# test_strip_v0_1_r1_2.net
KiCad netlist of a schematic drawn in EAGLE
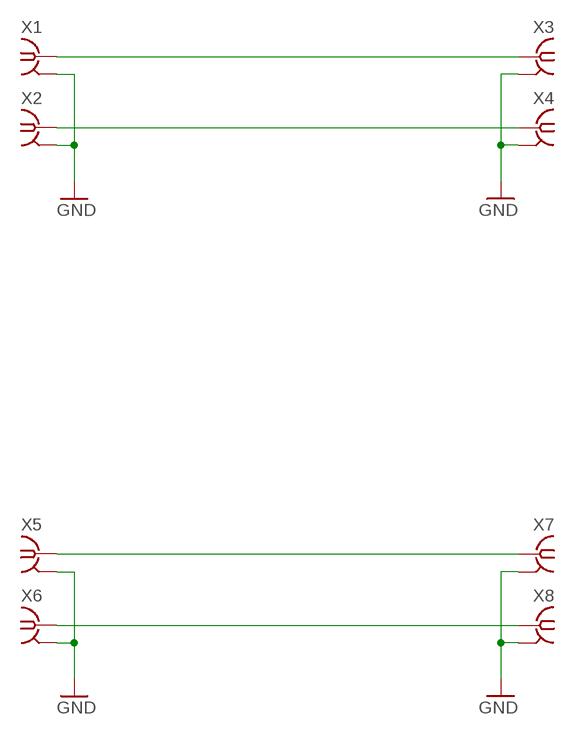
[diagram p0: schematic, sheet 1]

(export (version "E")
  (design (tool "Eeschema 10.0.6"))
  (components
    (comp (ref "X1")
      (value "BU-SMA-E-ND")
      (footprint "eagle-import:SMA-EDGE_ND")
      (libsource (lib "eagle-import") (part "BU-SMA-E-ND"))
    )
    (comp (ref "X2")
      (value "BU-SMA-E-ND")
      (footprint "eagle-import:SMA-EDGE_ND")
      (libsource (lib "eagle-import") (part "BU-SMA-E-ND"))
    )
    (comp (ref "X3")
      (value "BU-SMA-E-ND")
      (footprint "eagle-import:SMA-EDGE_ND")
      (libsource (lib "eagle-import") (part "BU-SMA-E-ND"))
    )
    (comp (ref "X4")
      (value "BU-SMA-E-ND")
      (footprint "eagle-import:SMA-EDGE_ND")
      (libsource (lib "eagle-import") (part "BU-SMA-E-ND"))
    )
    (comp (ref "X5")
      (value "BU-SMA-E-ND")
      (footprint "eagle-import:SMA-EDGE_ND")
      (libsource (lib "eagle-import") (part "BU-SMA-E-ND"))
    )
    (comp (ref "X6")
      (value "BU-SMA-E-ND")
      (footprint "eagle-import:SMA-EDGE_ND")
      (libsource (lib "eagle-import") (part "BU-SMA-E-ND"))
    )
    (comp (ref "X7")
      (value "BU-SMA-E-ND")
      (footprint "eagle-import:SMA-EDGE_ND")
      (libsource (lib "eagle-import") (part "BU-SMA-E-ND"))
    )
    (comp (ref "X8")
      (value "BU-SMA-E-ND")
      (footprint "eagle-import:SMA-EDGE_ND")
      (libsource (lib "eagle-import") (part "BU-SMA-E-ND"))
    )
  )
  (nets
    (net (code "1") (name "GND") (class "Default")
      (node (ref "X1") (pin "2@3") (pinfunction "2_2@3") (pintype "passive"))
      (node (ref "X1") (pin "2@4") (pinfunction "2_2@4") (pintype "passive"))
      (node (ref "X2") (pin "2@3") (pinfunction "2_2@3") (pintype "passive"))
      (node (ref "X2") (pin "2@4") (pinfunction "2_2@4") (pintype "passive"))
      (node (ref "X3") (pin "2@3") (pinfunction "2_2@3") (pintype "passive"))
      (node (ref "X3") (pin "2@4") (pinfunction "2_2@4") (pintype "passive"))
      (node (ref "X4") (pin "2@3") (pinfunction "2_2@3") (pintype "passive"))
      (node (ref "X4") (pin "2@4") (pinfunction "2_2@4") (pintype "passive"))
      (node (ref "X5") (pin "2@3") (pinfunction "2_2@3") (pintype "passive"))
      (node (ref "X5") (pin "2@4") (pinfunction "2_2@4") (pintype "passive"))
      (node (ref "X6") (pin "2@3") (pinfunction "2_2@3") (pintype "passive"))
      (node (ref "X6") (pin "2@4") (pinfunction "2_2@4") (pintype "passive"))
      (node (ref "X7") (pin "2@3") (pinfunction "2_2@3") (pintype "passive"))
      (node (ref "X7") (pin "2@4") (pinfunction "2_2@4") (pintype "passive"))
      (node (ref "X8") (pin "2@3") (pinfunction "2_2@3") (pintype "passive"))
      (node (ref "X8") (pin "2@4") (pinfunction "2_2@4") (pintype "passive"))
    )
    (net (code "2") (name "Net-(X1-Pad1)") (class "Default")
      (node (ref "X1") (pin "1") (pinfunction "1_1") (pintype "passive"))
      (node (ref "X3") (pin "1") (pinfunction "1_1") (pintype "passive"))
    )
    (net (code "3") (name "Net-(X2-Pad1)") (class "Default")
      (node (ref "X2") (pin "1") (pinfunction "1_1") (pintype "passive"))
      (node (ref "X4") (pin "1") (pinfunction "1_1") (pintype "passive"))
    )
    (net (code "4") (name "Net-(X5-Pad1)") (class "Default")
      (node (ref "X5") (pin "1") (pinfunction "1_1") (pintype "passive"))
      (node (ref "X7") (pin "1") (pinfunction "1_1") (pintype "passive"))
    )
    (net (code "5") (name "Net-(X6-Pad1)") (class "Default")
      (node (ref "X6") (pin "1") (pinfunction "1_1") (pintype "passive"))
      (node (ref "X8") (pin "1") (pinfunction "1_1") (pintype "passive"))
    )
  )
)
